# 02_MCU.net
KiCad netlist of a schematic drawn in Altium Designer
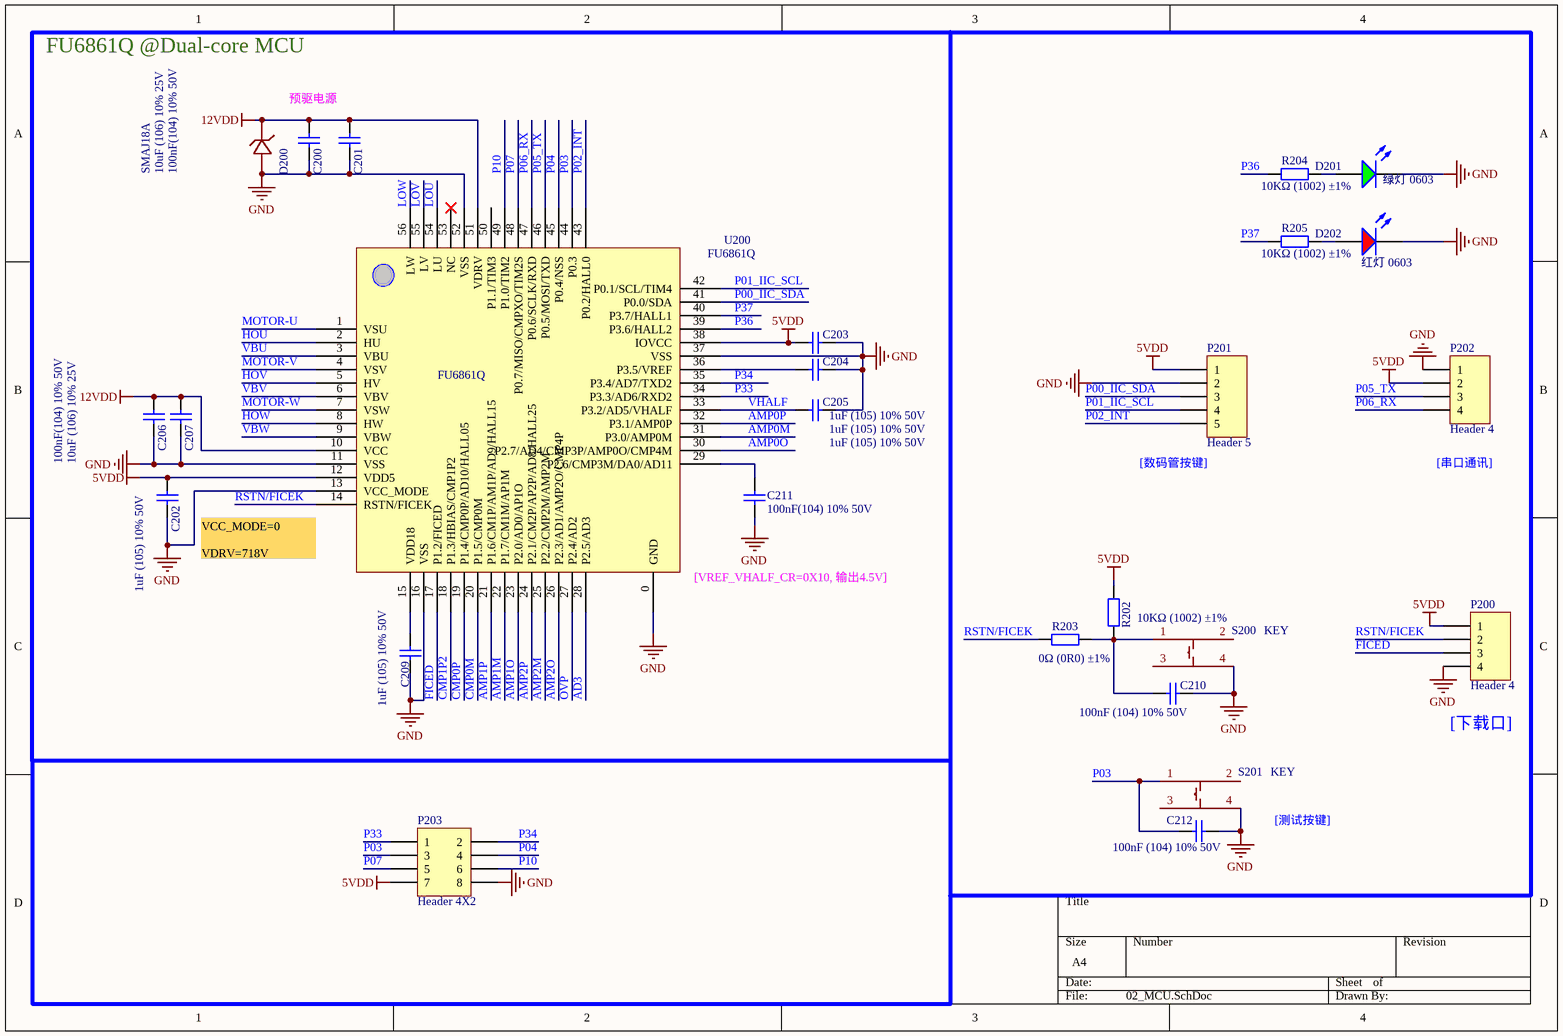
[diagram p0: 02_MCU.SchDoc]

(export (version "E")
  (design (tool "Eeschema 10.0.6"))
  (components
    (comp (ref "C200")
      (value "10uF (106) 10% 25V")
      (footprint "0805_C")
      (description "贴片电容")
      (libsource (lib "Miscellaneous Devices LC") (part "0805 10uF (106) 10% 25V"))
    )
    (comp (ref "C201")
      (value "100nF(104) 10% 50V")
      (footprint "0805_C")
      (description "贴片电容")
      (libsource (lib "Miscellaneous Devices LC") (part "0805 100nF(104) 10% 50V"))
    )
    (comp (ref "C202")
      (value "1uF (105) 10% 50V")
      (footprint "0805_C")
      (description "贴片电容")
      (libsource (lib "Miscellaneous Devices LC") (part "0805 1uF (105) 10% 50V"))
    )
    (comp (ref "C203")
      (value "1uF (105) 10% 50V")
      (footprint "0805_C")
      (description "贴片电容")
      (libsource (lib "Miscellaneous Devices LC") (part "0805 1uF (105) 10% 50V"))
    )
    (comp (ref "C204")
      (value "1uF (105) 10% 50V")
      (footprint "0805_C")
      (description "贴片电容")
      (libsource (lib "Miscellaneous Devices LC") (part "0805 1uF (105) 10% 50V"))
    )
    (comp (ref "C205")
      (value "1uF (105) 10% 50V")
      (footprint "0805_C")
      (description "贴片电容")
      (libsource (lib "Miscellaneous Devices LC") (part "0805 1uF (105) 10% 50V"))
    )
    (comp (ref "C206")
      (value "10uF (106) 10% 25V")
      (footprint "0805_C")
      (description "贴片电容")
      (libsource (lib "Miscellaneous Devices LC") (part "0805 10uF (106) 10% 25V"))
    )
    (comp (ref "C207")
      (value "100nF(104) 10% 50V")
      (footprint "0805_C")
      (description "贴片电容")
      (libsource (lib "Miscellaneous Devices LC") (part "0805 100nF(104) 10% 50V"))
    )
    (comp (ref "C209")
      (value "1uF (105) 10% 50V")
      (footprint "0805_C")
      (description "贴片电容")
      (libsource (lib "Miscellaneous Devices LC") (part "0805 1uF (105) 10% 50V"))
    )
    (comp (ref "C210")
      (value "100nF (104) 10% 50V")
      (footprint "0603_C")
      (description "贴片电容")
      (libsource (lib "Miscellaneous Devices LC") (part "0603 100nF (104) 10% 50V"))
    )
    (comp (ref "C211")
      (value "100nF(104) 10% 50V")
      (footprint "0805_C")
      (description "贴片电容")
      (libsource (lib "Miscellaneous Devices LC") (part "0805 100nF(104) 10% 50V"))
    )
    (comp (ref "C212")
      (value "100nF (104) 10% 50V")
      (footprint "0603_C")
      (description "贴片电容")
      (libsource (lib "Miscellaneous Devices LC") (part "0603 100nF (104) 10% 50V"))
    )
    (comp (ref "D200")
      (value "SMAJ18A")
      (footprint "SMAJ18A")
      (description "C435545")
      (libsource (lib "Schlibv2") (part "SMAJ18A"))
    )
    (comp (ref "D201")
      (value "绿灯 0603")
      (footprint "0603_LED_S1")
      (description "发光二极管")
      (libsource (lib "Miscellaneous Devices LC") (part "0603 绿灯"))
    )
    (comp (ref "D202")
      (value "红灯 0603")
      (footprint "0603_LED_S1")
      (description "发光二极管")
      (libsource (lib "Miscellaneous Devices LC") (part "0603 红灯"))
    )
    (comp (ref "P200")
      (value "Header 4")
      (footprint "HDR1X4")
      (description "Header, 4-Pin")
      (fields (field (name "PUBLISHER") "Altium Limited"))
      (libsource (lib "Miscellaneous Connectors") (part "Header 4"))
    )
    (comp (ref "P201")
      (value "Header 5")
      (footprint "HDR1X5")
      (description "Header, 5-Pin")
      (fields (field (name "PUBLISHER") "Altium Limited"))
      (libsource (lib "Miscellaneous Connectors") (part "Header 5"))
    )
    (comp (ref "P202")
      (value "Header 4")
      (footprint "HDR1X4")
      (description "Header, 4-Pin")
      (fields (field (name "PUBLISHER") "Altium Limited"))
      (libsource (lib "Miscellaneous Connectors") (part "Header 4"))
    )
    (comp (ref "P203")
      (value "Header 4X2")
      (footprint "HDR2X4")
      (description "Header, 4-Pin, Dual row")
      (fields (field (name "PUBLISHER") "Altium Limited"))
      (libsource (lib "Miscellaneous Connectors") (part "Header 4X2"))
    )
    (comp (ref "R202")
      (value "10KΩ (1002) ±1%")
      (footprint "0603_R")
      (description "贴片电阻")
      (libsource (lib "Miscellaneous Devices LC") (part "0603 10KΩ (1002) 1%"))
    )
    (comp (ref "R203")
      (value "0Ω (0R0) ±1%")
      (footprint "0603_R")
      (description "贴片电阻")
      (libsource (lib "Miscellaneous Devices LC") (part "0603 0Ω (0R0) 1%"))
    )
    (comp (ref "R204")
      (value "10KΩ (1002) ±1%")
      (footprint "0805_R")
      (description "贴片电阻")
      (libsource (lib "Miscellaneous Devices LC") (part "0805 10KΩ (1002) 1%"))
    )
    (comp (ref "R205")
      (value "10KΩ (1002) ±1%")
      (footprint "0805_R")
      (description "贴片电阻")
      (libsource (lib "Miscellaneous Devices LC") (part "0805 10KΩ (1002) 1%"))
    )
    (comp (ref "S200")
      (value "KEY")
      (footprint "KEY_WHITE")
      (description "白色方块")
      (libsource (lib "Schlibv2") (part "KEY"))
    )
    (comp (ref "S201")
      (value "KEY")
      (footprint "KEY_WHITE")
      (description "白色方块")
      (libsource (lib "Schlibv2") (part "KEY"))
    )
    (comp (ref "U200") (value "FU6861Q") (footprint "FU6861Q") (libsource (lib "Schlibv2") (part "FU6861Q")))
  )
  (nets
    (net (code "1") (name "/AD3") (class "Default")
      (node (ref "U200") (pin "28") (pinfunction "P2.5/AD3_28") (pintype "passive"))
    )
    (net (code "2") (name "/AMP0M") (class "Default")
      (node (ref "U200") (pin "31") (pinfunction "P3.0/AMP0M_31") (pintype "passive"))
    )
    (net (code "3") (name "/AMP0O") (class "Default")
      (node (ref "U200") (pin "30") (pinfunction "P2.7/AD4/CMP3P/AMP0O/CMP4M_30") (pintype "passive"))
    )
    (net (code "4") (name "/AMP0P") (class "Default")
      (node (ref "U200") (pin "32") (pinfunction "P3.1/AMP0P_32") (pintype "passive"))
    )
    (net (code "5") (name "/AMP1M") (class "Default")
      (node (ref "U200") (pin "22") (pinfunction "P1.7/CM1M/AP1M_22") (pintype "passive"))
    )
    (net (code "6") (name "/AMP1O") (class "Default")
      (node (ref "U200") (pin "23") (pinfunction "P2.0/AD0/AP1O_23") (pintype "passive"))
    )
    (net (code "7") (name "/AMP1P") (class "Default")
      (node (ref "U200") (pin "21") (pinfunction "P1.6/CM1P/AM1P/AD9/HALL15_21") (pintype "passive"))
    )
    (net (code "8") (name "/AMP2M") (class "Default")
      (node (ref "U200") (pin "25") (pinfunction "P2.2/CMP2M/AMP2M_25") (pintype "passive"))
    )
    (net (code "9") (name "/AMP2O") (class "Default")
      (node (ref "U200") (pin "26") (pinfunction "P2.3/AD1/AMP2O/CMP4P_26") (pintype "passive"))
    )
    (net (code "10") (name "/AMP2P") (class "Default")
      (node (ref "U200") (pin "24") (pinfunction "P2.1/CM2P/AP2P/AD8/HALL25_24") (pintype "passive"))
    )
    (net (code "11") (name "/CMP0M") (class "Default")
      (node (ref "U200") (pin "20") (pinfunction "P1.5/CMP0M_20") (pintype "passive"))
    )
    (net (code "12") (name "/CMP0P") (class "Default")
      (node (ref "U200") (pin "19") (pinfunction "P1.4/CMP0P/AD10/HALL05_19") (pintype "passive"))
    )
    (net (code "13") (name "/CMP1P2") (class "Default")
      (node (ref "U200") (pin "18") (pinfunction "P1.3/HBIAS/CMP1P2_18") (pintype "passive"))
    )
    (net (code "14") (name "/FICED") (class "Default")
      (node (ref "P200") (pin "3") (pinfunction "3_3") (pintype "passive"))
      (node (ref "U200") (pin "17") (pinfunction "P1.2/FICED_17") (pintype "passive"))
    )
    (net (code "15") (name "/HOU") (class "Default")
      (node (ref "U200") (pin "2") (pinfunction "HU_2") (pintype "passive"))
    )
    (net (code "16") (name "/HOV") (class "Default")
      (node (ref "U200") (pin "5") (pinfunction "HV_5") (pintype "passive"))
    )
    (net (code "17") (name "/HOW") (class "Default")
      (node (ref "U200") (pin "8") (pinfunction "HW_8") (pintype "passive"))
    )
    (net (code "18") (name "/LOU") (class "Default")
      (node (ref "U200") (pin "54") (pinfunction "LU_54") (pintype "passive"))
    )
    (net (code "19") (name "/LOV") (class "Default")
      (node (ref "U200") (pin "55") (pinfunction "LV_55") (pintype "passive"))
    )
    (net (code "20") (name "/LOW") (class "Default")
      (node (ref "U200") (pin "56") (pinfunction "LW_56") (pintype "passive"))
    )
    (net (code "21") (name "/MOTOR-U") (class "Default")
      (node (ref "U200") (pin "1") (pinfunction "VSU_1") (pintype "passive"))
    )
    (net (code "22") (name "/MOTOR-V") (class "Default")
      (node (ref "U200") (pin "4") (pinfunction "VSV_4") (pintype "passive"))
    )
    (net (code "23") (name "/MOTOR-W") (class "Default")
      (node (ref "U200") (pin "7") (pinfunction "VSW_7") (pintype "passive"))
    )
    (net (code "24") (name "/OVP") (class "Default")
      (node (ref "U200") (pin "27") (pinfunction "P2.4/AD2_27") (pintype "passive"))
    )
    (net (code "25") (name "/P00_IIC_SDA") (class "Default")
      (node (ref "P201") (pin "3") (pinfunction "3_3") (pintype "passive"))
      (node (ref "U200") (pin "41") (pinfunction "P0.0/SDA_41") (pintype "passive"))
    )
    (net (code "26") (name "/P01_IIC_SCL") (class "Default")
      (node (ref "P201") (pin "4") (pinfunction "4_4") (pintype "passive"))
      (node (ref "U200") (pin "42") (pinfunction "P0.1/SCL/TIM4_42") (pintype "passive"))
    )
    (net (code "27") (name "/P02_INT") (class "Default")
      (node (ref "P201") (pin "5") (pinfunction "5_5") (pintype "passive"))
      (node (ref "U200") (pin "43") (pinfunction "P0.2/HALL0_43") (pintype "passive"))
    )
    (net (code "28") (name "/P03") (class "Default")
      (node (ref "C212") (pin "2") (pinfunction "2_2") (pintype "passive"))
      (node (ref "P203") (pin "3") (pinfunction "3_3") (pintype "passive"))
      (node (ref "S201") (pin "1") (pinfunction "1_1") (pintype "passive"))
      (node (ref "U200") (pin "44") (pinfunction "P0.3_44") (pintype "passive"))
    )
    (net (code "29") (name "/P04") (class "Default")
      (node (ref "P203") (pin "4") (pinfunction "4_4") (pintype "passive"))
      (node (ref "U200") (pin "45") (pinfunction "P0.4/NSS_45") (pintype "passive"))
    )
    (net (code "30") (name "/P05_TX") (class "Default")
      (node (ref "P202") (pin "3") (pinfunction "3_3") (pintype "passive"))
      (node (ref "U200") (pin "46") (pinfunction "P0.5/MOSI/TXD_46") (pintype "passive"))
    )
    (net (code "31") (name "/P06_RX") (class "Default")
      (node (ref "P202") (pin "4") (pinfunction "4_4") (pintype "passive"))
      (node (ref "U200") (pin "47") (pinfunction "P0.6/SCLK/RXD_47") (pintype "passive"))
    )
    (net (code "32") (name "/P07") (class "Default")
      (node (ref "P203") (pin "5") (pinfunction "5_5") (pintype "passive"))
      (node (ref "U200") (pin "48") (pinfunction "P0.7/MISO/CMPXO/TIM2S_48") (pintype "passive"))
    )
    (net (code "33") (name "/P10") (class "Default")
      (node (ref "P203") (pin "6") (pinfunction "6_6") (pintype "passive"))
      (node (ref "U200") (pin "49") (pinfunction "P1.0/TIM2_49") (pintype "passive"))
    )
    (net (code "34") (name "/P33") (class "Default")
      (node (ref "P203") (pin "1") (pinfunction "1_1") (pintype "passive"))
      (node (ref "U200") (pin "34") (pinfunction "P3.3/AD6/RXD2_34") (pintype "passive"))
    )
    (net (code "35") (name "/P34") (class "Default")
      (node (ref "P203") (pin "2") (pinfunction "2_2") (pintype "passive"))
      (node (ref "U200") (pin "35") (pinfunction "P3.4/AD7/TXD2_35") (pintype "passive"))
    )
    (net (code "36") (name "/P36") (class "Default")
      (node (ref "R204") (pin "1") (pinfunction "1_1") (pintype "passive"))
      (node (ref "U200") (pin "39") (pinfunction "P3.6/HALL2_39") (pintype "passive"))
    )
    (net (code "37") (name "/P37") (class "Default")
      (node (ref "R205") (pin "1") (pinfunction "1_1") (pintype "passive"))
      (node (ref "U200") (pin "40") (pinfunction "P3.7/HALL1_40") (pintype "passive"))
    )
    (net (code "38") (name "/RSTN{slash}FICEK") (class "Default")
      (node (ref "P200") (pin "2") (pinfunction "2_2") (pintype "passive"))
      (node (ref "R203") (pin "1") (pinfunction "1_1") (pintype "passive"))
      (node (ref "U200") (pin "14") (pinfunction "RSTN/FICEK_14") (pintype "passive"))
    )
    (net (code "39") (name "/VBU") (class "Default")
      (node (ref "U200") (pin "3") (pinfunction "VBU_3") (pintype "passive"))
    )
    (net (code "40") (name "/VBV") (class "Default")
      (node (ref "U200") (pin "6") (pinfunction "VBV_6") (pintype "passive"))
    )
    (net (code "41") (name "/VBW") (class "Default")
      (node (ref "U200") (pin "9") (pinfunction "VBW_9") (pintype "passive"))
    )
    (net (code "42") (name "/VHALF") (class "Default")
      (node (ref "C205") (pin "1") (pinfunction "1_1") (pintype "passive"))
      (node (ref "U200") (pin "33") (pinfunction "P3.2/AD5/VHALF_33") (pintype "passive"))
    )
    (net (code "43") (name "5VDD") (class "Default")
      (node (ref "C202") (pin "2") (pinfunction "2_2") (pintype "passive"))
      (node (ref "C203") (pin "1") (pinfunction "1_1") (pintype "passive"))
      (node (ref "P200") (pin "1") (pinfunction "1_1") (pintype "passive"))
      (node (ref "P201") (pin "1") (pinfunction "1_1") (pintype "passive"))
      (node (ref "P202") (pin "2") (pinfunction "2_2") (pintype "passive"))
      (node (ref "P203") (pin "7") (pinfunction "7_7") (pintype "passive"))
      (node (ref "R202") (pin "2") (pinfunction "2_2") (pintype "passive"))
      (node (ref "U200") (pin "12") (pinfunction "VDD5_12") (pintype "passive"))
      (node (ref "U200") (pin "38") (pinfunction "IOVCC_38") (pintype "passive"))
    )
    (net (code "44") (name "12VDD") (class "Default")
      (node (ref "C200") (pin "2") (pinfunction "2_2") (pintype "passive"))
      (node (ref "C201") (pin "2") (pinfunction "2_2") (pintype "passive"))
      (node (ref "C206") (pin "2") (pinfunction "2_2") (pintype "passive"))
      (node (ref "C207") (pin "2") (pinfunction "2_2") (pintype "passive"))
      (node (ref "D200") (pin "1") (pinfunction "C_1") (pintype "passive"))
      (node (ref "U200") (pin "10") (pinfunction "VCC_10") (pintype "passive"))
      (node (ref "U200") (pin "51") (pinfunction "VDRV_51") (pintype "passive"))
    )
    (net (code "45") (name "GND") (class "Default")
      (node (ref "C200") (pin "1") (pinfunction "1_1") (pintype "passive"))
      (node (ref "C201") (pin "1") (pinfunction "1_1") (pintype "passive"))
      (node (ref "C202") (pin "1") (pinfunction "1_1") (pintype "passive"))
      (node (ref "C203") (pin "2") (pinfunction "2_2") (pintype "passive"))
      (node (ref "C204") (pin "2") (pinfunction "2_2") (pintype "passive"))
      (node (ref "C205") (pin "2") (pinfunction "2_2") (pintype "passive"))
      (node (ref "C206") (pin "1") (pinfunction "1_1") (pintype "passive"))
      (node (ref "C207") (pin "1") (pinfunction "1_1") (pintype "passive"))
      (node (ref "C209") (pin "1") (pinfunction "1_1") (pintype "passive"))
      (node (ref "C210") (pin "2") (pinfunction "2_2") (pintype "passive"))
      (node (ref "C211") (pin "2") (pinfunction "2_2") (pintype "passive"))
      (node (ref "C212") (pin "1") (pinfunction "1_1") (pintype "passive"))
      (node (ref "D200") (pin "2") (pinfunction "A_2") (pintype "passive"))
      (node (ref "D201") (pin "K") (pinfunction "K_K") (pintype "passive"))
      (node (ref "D202") (pin "K") (pinfunction "K_K") (pintype "passive"))
      (node (ref "P200") (pin "4") (pinfunction "4_4") (pintype "passive"))
      (node (ref "P201") (pin "2") (pinfunction "2_2") (pintype "passive"))
      (node (ref "P202") (pin "1") (pinfunction "1_1") (pintype "passive"))
      (node (ref "P203") (pin "8") (pinfunction "8_8") (pintype "passive"))
      (node (ref "S200") (pin "4") (pinfunction "4_4") (pintype "passive"))
      (node (ref "S201") (pin "4") (pinfunction "4_4") (pintype "passive"))
      (node (ref "U200") (pin "0") (pinfunction "GND_0") (pintype "passive"))
      (node (ref "U200") (pin "11") (pinfunction "VSS_11") (pintype "passive"))
      (node (ref "U200") (pin "13") (pinfunction "VCC_MODE_13") (pintype "passive"))
      (node (ref "U200") (pin "16") (pinfunction "VSS_16") (pintype "passive"))
      (node (ref "U200") (pin "37") (pinfunction "VSS_37") (pintype "passive"))
      (node (ref "U200") (pin "52") (pinfunction "VSS_52") (pintype "passive"))
    )
    (net (code "46") (name "Net-(C210-Pad1)") (class "Default")
      (node (ref "C210") (pin "1") (pinfunction "1_1") (pintype "passive"))
      (node (ref "R202") (pin "1") (pinfunction "1_1") (pintype "passive"))
      (node (ref "R203") (pin "2") (pinfunction "2_2") (pintype "passive"))
      (node (ref "S200") (pin "1") (pinfunction "1_1") (pintype "passive"))
    )
    (net (code "47") (name "Net-(D201-PadA)") (class "Default")
      (node (ref "D201") (pin "A") (pinfunction "A_A") (pintype "passive"))
      (node (ref "R204") (pin "2") (pinfunction "2_2") (pintype "passive"))
    )
    (net (code "48") (name "Net-(D202-PadA)") (class "Default")
      (node (ref "D202") (pin "A") (pinfunction "A_A") (pintype "passive"))
      (node (ref "R205") (pin "2") (pinfunction "2_2") (pintype "passive"))
    )
    (net (code "49") (name "Net-(U200-P2.6{slash}CMP3M{slash}DA0{slash}AD11)") (class "Default")
      (node (ref "C211") (pin "1") (pinfunction "1_1") (pintype "passive"))
      (node (ref "U200") (pin "29") (pinfunction "P2.6/CMP3M/DA0/AD11_29") (pintype "passive"))
    )
    (net (code "50") (name "Net-(U200-P3.5{slash}VREF)") (class "Default")
      (node (ref "C204") (pin "1") (pinfunction "1_1") (pintype "passive"))
      (node (ref "U200") (pin "36") (pinfunction "P3.5/VREF_36") (pintype "passive"))
    )
    (net (code "51") (name "Net-(U200-VDD18)") (class "Default")
      (node (ref "C209") (pin "2") (pinfunction "2_2") (pintype "passive"))
      (node (ref "U200") (pin "15") (pinfunction "VDD18_15") (pintype "passive"))
    )
    (net (code "52") (name "unconnected-(S200-Pad2)") (class "Default")
      (node (ref "S200") (pin "2") (pinfunction "2_2") (pintype "passive"))
    )
    (net (code "53") (name "unconnected-(S200-Pad3)") (class "Default")
      (node (ref "S200") (pin "3") (pinfunction "3_3") (pintype "passive"))
    )
    (net (code "54") (name "unconnected-(S201-Pad2)") (class "Default")
      (node (ref "S201") (pin "2") (pinfunction "2_2") (pintype "passive"))
    )
    (net (code "55") (name "unconnected-(S201-Pad3)") (class "Default")
      (node (ref "S201") (pin "3") (pinfunction "3_3") (pintype "passive"))
    )
    (net (code "56") (name "unconnected-(U200-NC-Pad53)") (class "Default")
      (node (ref "U200") (pin "53") (pinfunction "NC_53") (pintype "passive+no_connect"))
    )
    (net (code "57") (name "unconnected-(U200-P1.1{slash}TIM3-Pad50)") (class "Default")
      (node (ref "U200") (pin "50") (pinfunction "P1.1/TIM3_50") (pintype "passive"))
    )
  )
)
